# receptor_same.net
KiCad netlist of a schematic drawn in EAGLE
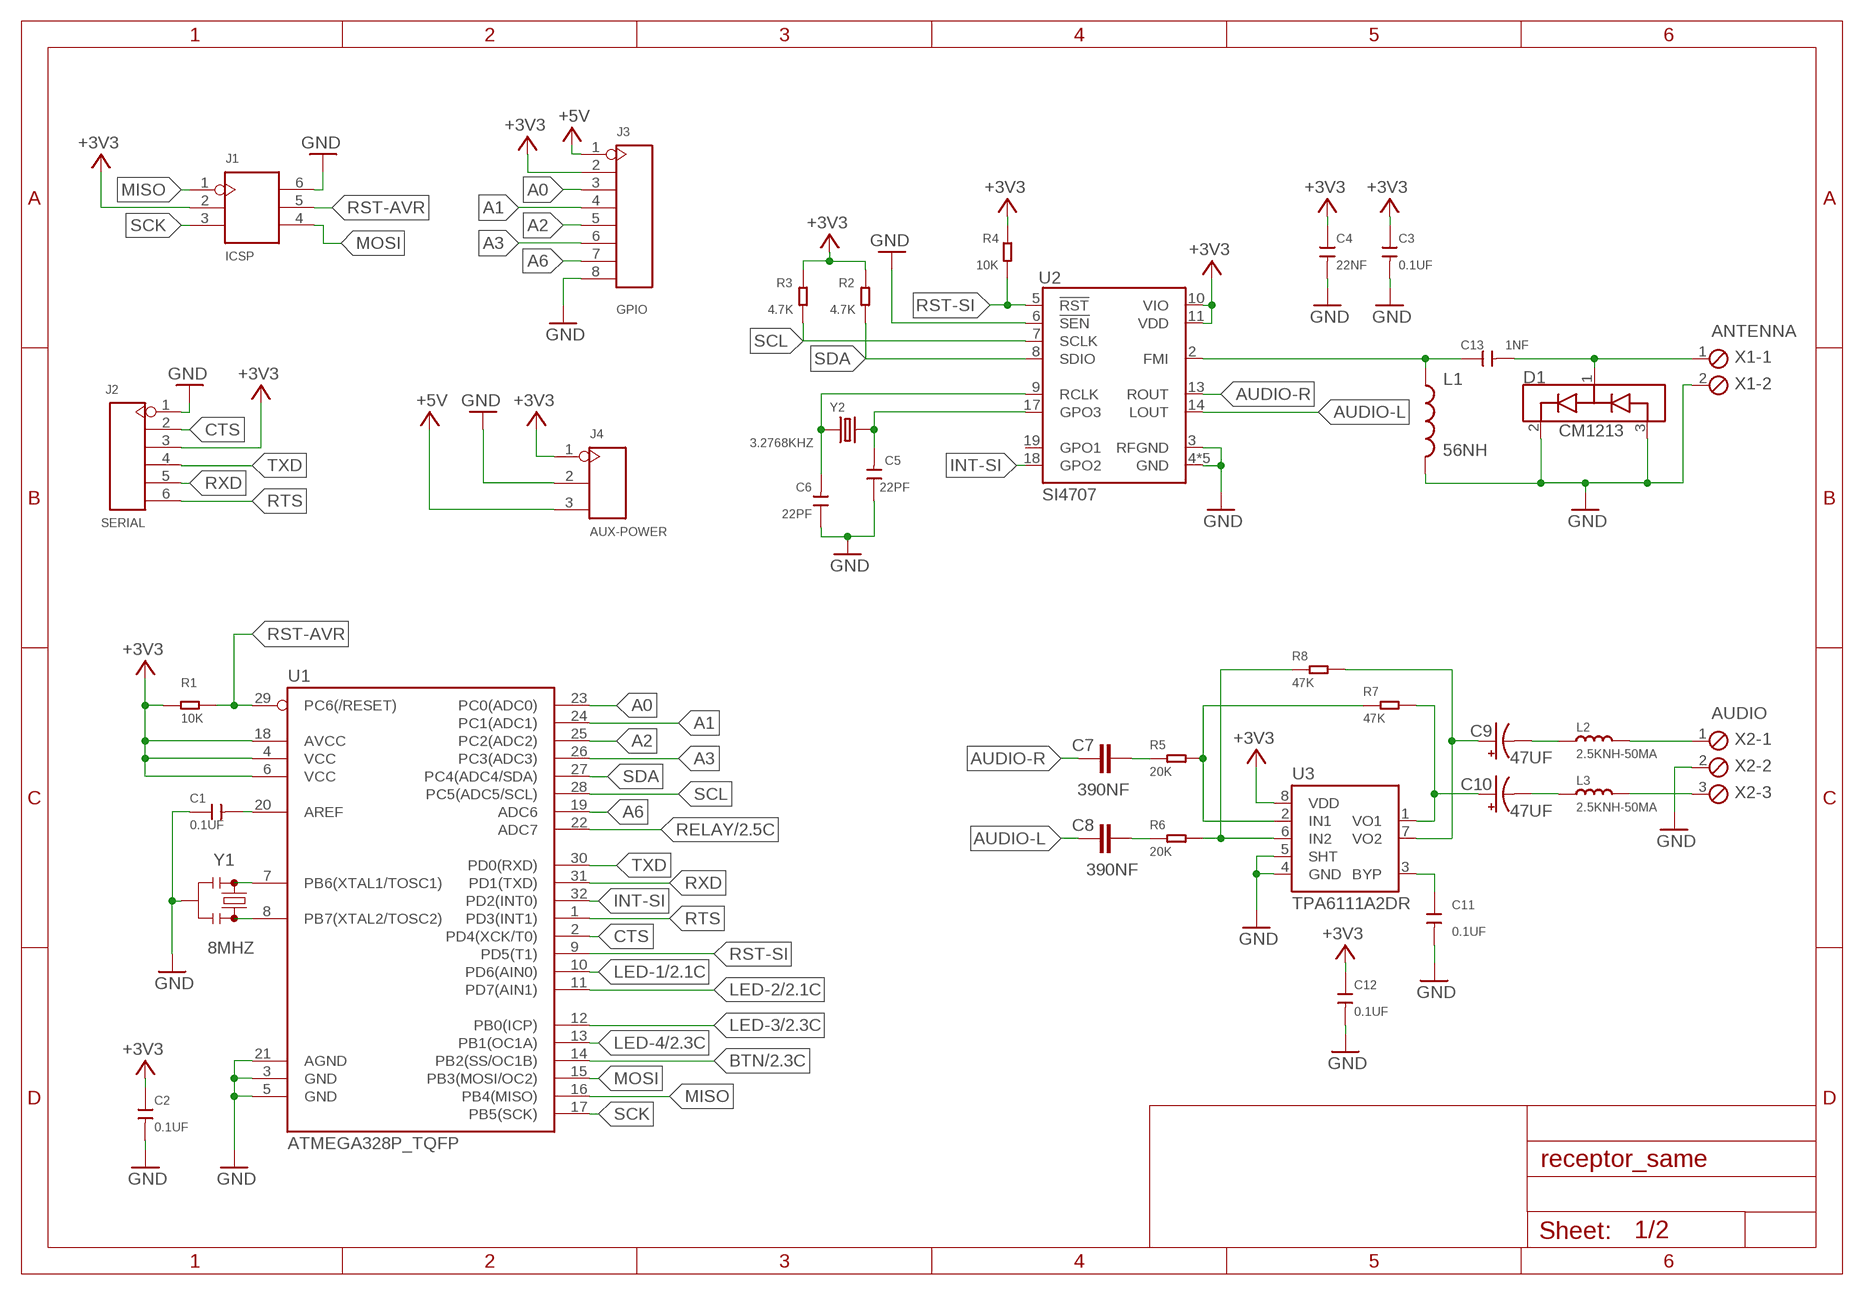
[diagram p0: schematic, sheet 1]
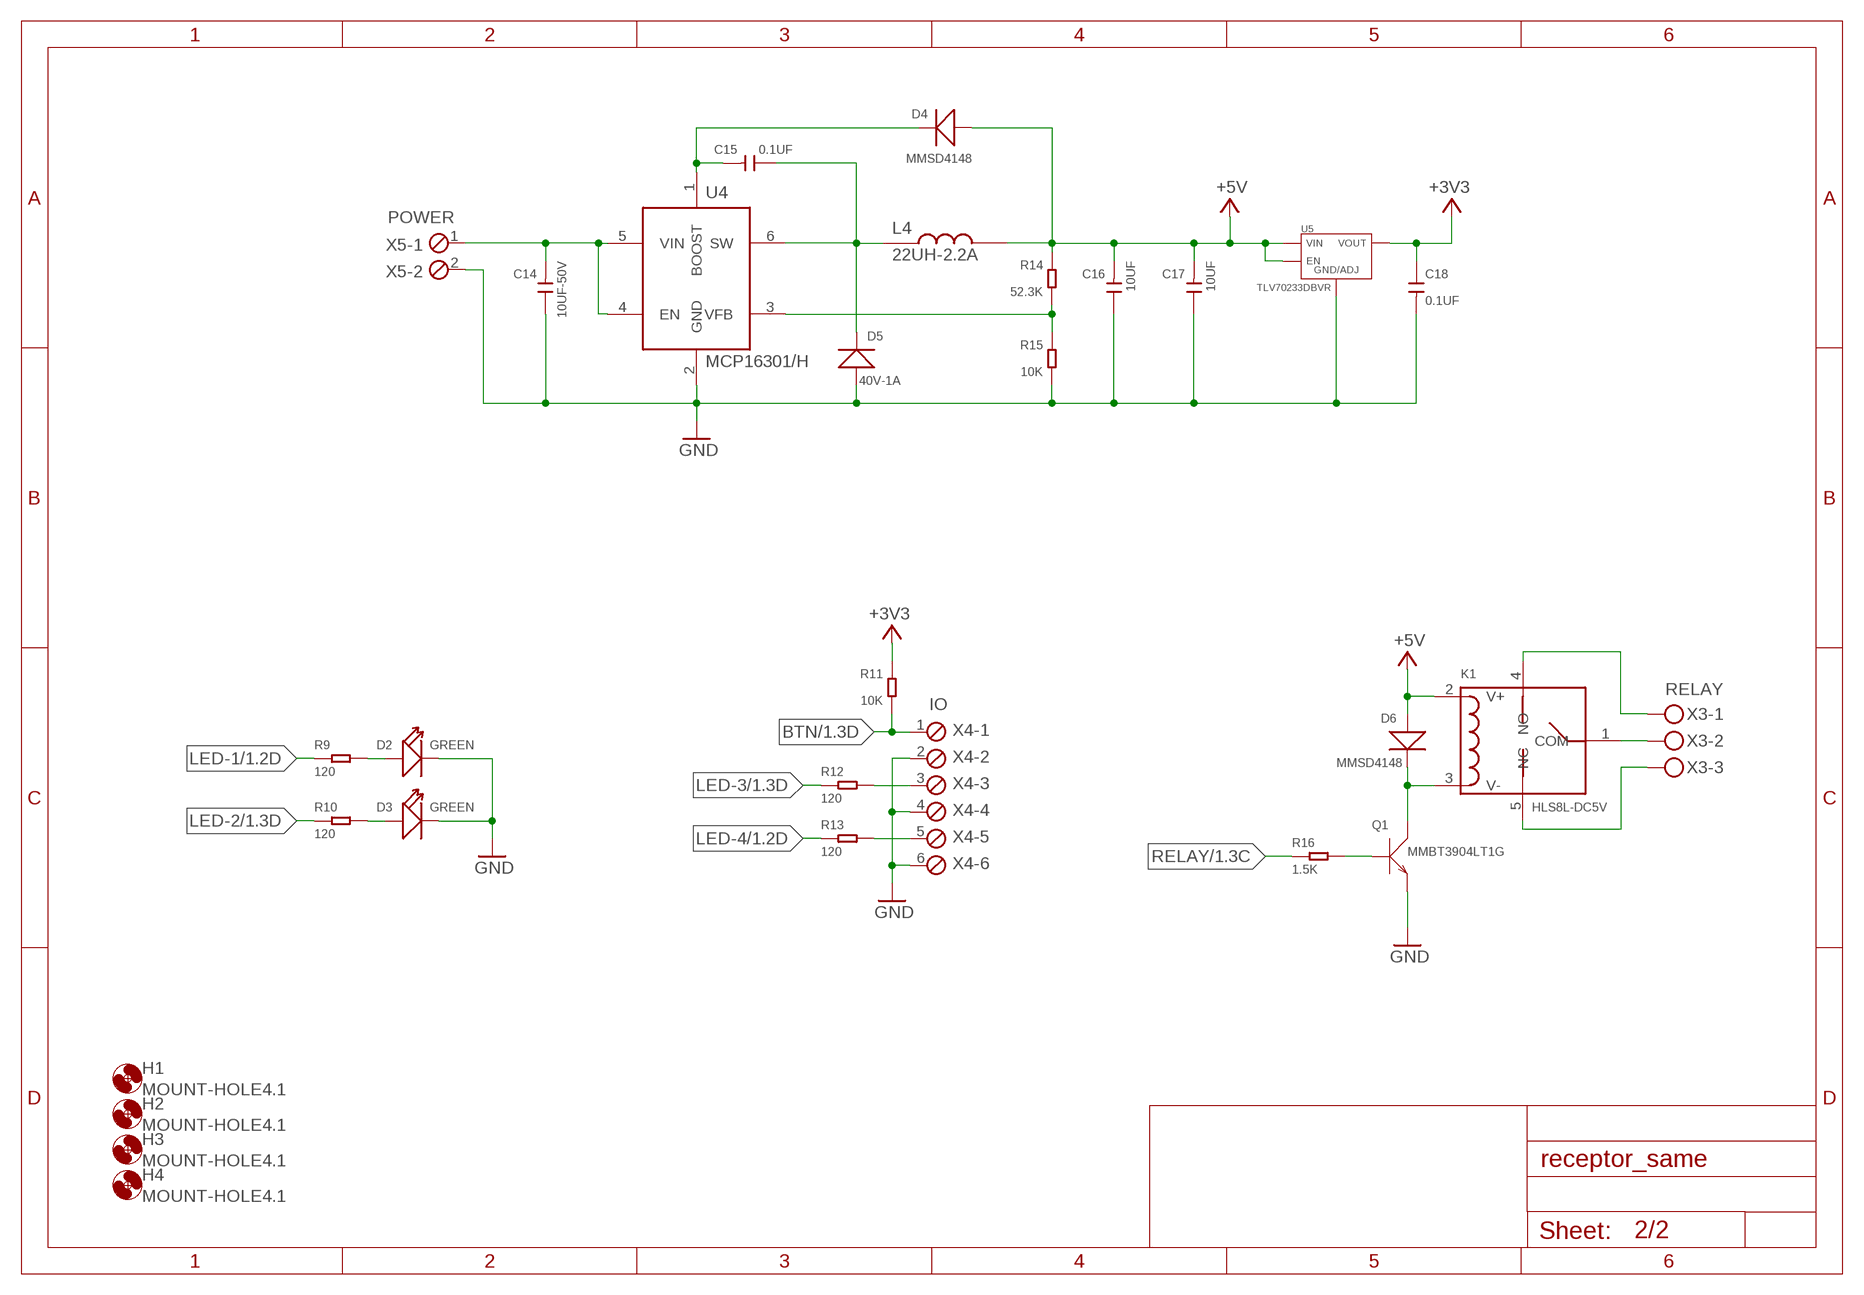
[diagram p1: schematic, sheet 2]

(export (version "E")
  (design (tool "Eeschema 10.0.6"))
  (components
    (comp (ref "C14")
      (value "10UF-50V")
      (footprint "eagle-import:C1206")
      (fields (field (name "MPN") "CC1206KKX5R8BB106") (field (name "MPN_1") "CL31A106KBHNNNE"))
      (libsource (lib "eagle-import") (part "CERAMIC-10UF-25V-10%-X5R(1206)"))
    )
    (comp (ref "C15")
      (value "0.1UF")
      (footprint "eagle-import:C0603")
      (fields (field (name "MPN") "CC0603KRX7R9BB104"))
      (libsource (lib "eagle-import") (part "CERAMIC-100NF-50V-10%-X7R(0603)"))
    )
    (comp (ref "C16")
      (value "10UF")
      (footprint "eagle-import:C0603")
      (fields (field (name "MPN") "CC0603MRX5R5BB106"))
      (libsource (lib "eagle-import") (part "CERAMIC-10UF-6.3V-20%-X5R(0603)"))
    )
    (comp (ref "C17")
      (value "10UF")
      (footprint "eagle-import:C0603")
      (fields (field (name "MPN") "CC0603MRX5R5BB106"))
      (libsource (lib "eagle-import") (part "CERAMIC-10UF-6.3V-20%-X5R(0603)"))
    )
    (comp (ref "C18")
      (value "0.1UF")
      (footprint "eagle-import:C0603")
      (fields (field (name "MPN") "CC0603KRX7R9BB104"))
      (libsource (lib "eagle-import") (part "CERAMIC-100NF-50V-10%-X7R(0603)"))
    )
    (comp (ref "D2")
      (value "GREEN")
      (footprint "eagle-import:LED-0805")
      (fields (field (name "MPN") "17-215SYGC/S530-E2/TR8"))
      (libsource (lib "eagle-import") (part "SMD-LED-CLEAR-GREEN(0805)"))
    )
    (comp (ref "D3")
      (value "GREEN")
      (footprint "eagle-import:LED-0805")
      (fields (field (name "MPN") "17-215SYGC/S530-E2/TR8"))
      (libsource (lib "eagle-import") (part "SMD-LED-CLEAR-GREEN(0805)"))
    )
    (comp (ref "D4")
      (value "MMSD4148")
      (footprint "eagle-import:SOD-123")
      (libsource (lib "eagle-import") (part "SMD-DIODE-100V-200MA(SOD-123)"))
    )
    (comp (ref "D5")
      (value "40V-1A")
      (footprint "eagle-import:DO-214AC")
      (fields (field (name "MPN") "1N5819"))
      (libsource (lib "eagle-import") (part "SMD-DIODE-SCHOTTKY-40V-1A(DO-214AC)"))
    )
    (comp (ref "D6")
      (value "MMSD4148")
      (footprint "eagle-import:SOD-123")
      (libsource (lib "eagle-import") (part "SMD-DIODE-100V-200MA(SOD-123)"))
    )
    (comp (ref "H1")
      (value "MOUNT-HOLE4.1")
      (footprint "eagle-import:4,1")
      (libsource (lib "eagle-import") (part "MOUNT-HOLE4.1"))
    )
    (comp (ref "H2")
      (value "MOUNT-HOLE4.1")
      (footprint "eagle-import:4,1")
      (libsource (lib "eagle-import") (part "MOUNT-HOLE4.1"))
    )
    (comp (ref "H3")
      (value "MOUNT-HOLE4.1")
      (footprint "eagle-import:4,1")
      (libsource (lib "eagle-import") (part "MOUNT-HOLE4.1"))
    )
    (comp (ref "H4")
      (value "MOUNT-HOLE4.1")
      (footprint "eagle-import:4,1")
      (libsource (lib "eagle-import") (part "MOUNT-HOLE4.1"))
    )
    (comp (ref "K1")
      (value "HLS8L-DC5V")
      (footprint "eagle-import:REY5-19.0X15.0X15.0MM")
      (fields (field (name "MPN") "HLS8L-DC5V-S-C"))
      (libsource (lib "eagle-import") (part "RELAY-HLS8L-DC5V-S-CHLS8L-DC5V-S-C"))
    )
    (comp (ref "L4")
      (value "22UH-2.2A")
      (footprint "eagle-import:L2826")
      (fields (field (name "MPN") "SHC0603-220M "))
      (libsource (lib "eagle-import") (part "303010525_22UH_7.1X6.6MM"))
    )
    (comp (ref "Q1")
      (value "MMBT3904LT1G")
      (footprint "eagle-import:SOT-23")
      (libsource (lib "eagle-import") (part "SMD-TRANSISTORS-NPN-40V-200MA-MMBT3904LT1G(SOT-23)"))
    )
    (comp (ref "R9")
      (value "120")
      (footprint "eagle-import:R0805")
      (fields (field (name "MPN") "RC0805JR-071KL") (field (name "MPN_1") "RC0805JR-07120RL"))
      (libsource (lib "eagle-import") (part "SMD-RES-120R-5%-1/8W(0805)"))
    )
    (comp (ref "R10")
      (value "120")
      (footprint "eagle-import:R0805")
      (fields (field (name "MPN") "RC0805JR-071KL") (field (name "MPN_1") "RC0805JR-07120RL"))
      (libsource (lib "eagle-import") (part "SMD-RES-120R-5%-1/8W(0805)"))
    )
    (comp (ref "R11")
      (value "10K")
      (footprint "eagle-import:R0603")
      (fields (field (name "MPN") "RC0603JR-0710KL"))
      (libsource (lib "eagle-import") (part "SMD-RES-10K-5%-1/10W(0603)"))
    )
    (comp (ref "R12")
      (value "120")
      (footprint "eagle-import:R0805")
      (fields (field (name "MPN") "RC0805JR-071KL") (field (name "MPN_1") "RC0805JR-07120RL"))
      (libsource (lib "eagle-import") (part "SMD-RES-120R-5%-1/8W(0805)"))
    )
    (comp (ref "R13")
      (value "120")
      (footprint "eagle-import:R0805")
      (fields (field (name "MPN") "RC0805JR-071KL") (field (name "MPN_1") "RC0805JR-07120RL"))
      (libsource (lib "eagle-import") (part "SMD-RES-120R-5%-1/8W(0805)"))
    )
    (comp (ref "R14")
      (value "52.3K")
      (footprint "eagle-import:R0603")
      (fields (field (name "MPN") "RC0603JR-0751KL") (field (name "MPN_1") "WR06X5232FTL"))
      (libsource (lib "eagle-import") (part "SMD-RES-51K-5%-1/10W(0603)"))
    )
    (comp (ref "R15")
      (value "10K")
      (footprint "eagle-import:R0603")
      (fields (field (name "MPN") "RC0603JR-0710KL"))
      (libsource (lib "eagle-import") (part "SMD-RES-10K-5%-1/10W(0603)"))
    )
    (comp (ref "R16")
      (value "1.5K")
      (footprint "eagle-import:R0603")
      (fields (field (name "MPN") "RC0603JR-071K5L"))
      (libsource (lib "eagle-import") (part "SMD-RES-1.5K-5%-1/10W(0603)"))
    )
    (comp (ref "U4")
      (value "MCP16301/H")
      (footprint "eagle-import:SOT23-6")
      (fields (field (name "MPN") "MCP16301T-I/CHY"))
      (libsource (lib "eagle-import") (part "MCP16301/H"))
    )
    (comp (ref "U5")
      (value "TLV70233DBVR")
      (footprint "eagle-import:SOT-23-5")
      (fields
        (field (name "HOUSEPART") "YES")
        (field (name "MPN") "MF-REG-SOT235-3.3V-300mA")
        (field (name "MPN_1") "TLV70233DBVR")
      )
      (libsource (lib "eagle-import") (part "TLV70233PDBVR"))
    )
    (comp (ref "X3")
      (value "RELAY")
      (footprint "eagle-import:MKDSN1,5_3-5,08")
      (fields (field (name "MPN") "1715734"))
      (libsource (lib "eagle-import") (part "MKDSN1,5/3-5,08"))
    )
    (comp (ref "X4")
      (value "IO")
      (footprint "eagle-import:6POL254")
      (fields (field (name "MPN") "1725698"))
      (libsource (lib "eagle-import") (part "MPT6"))
    )
    (comp (ref "X5")
      (value "POWER")
      (footprint "eagle-import:2POL254")
      (fields (field (name "MPN") "1725656"))
      (libsource (lib "eagle-import") (part "MPT2"))
    )
    (comp (ref "C1")
      (value "0.1UF")
      (footprint "eagle-import:C0603")
      (fields (field (name "MPN") "CC0603KRX7R9BB104"))
      (libsource (lib "eagle-import") (part "CERAMIC-100NF-50V-10%-X7R(0603)"))
    )
    (comp (ref "C2")
      (value "0.1UF")
      (footprint "eagle-import:C0603")
      (fields (field (name "MPN") "CC0603KRX7R9BB104"))
      (libsource (lib "eagle-import") (part "CERAMIC-100NF-50V-10%-X7R(0603)"))
    )
    (comp (ref "C3")
      (value "0.1UF")
      (footprint "eagle-import:C0603")
      (fields (field (name "MPN") "CC0603KRX7R9BB104"))
      (libsource (lib "eagle-import") (part "CERAMIC-100NF-50V-10%-X7R(0603)"))
    )
    (comp (ref "C4")
      (value "22NF")
      (footprint "eagle-import:C0603")
      (fields (field (name "MPN") "CC0603KRX7R9BB223"))
      (libsource (lib "eagle-import") (part "CERAMIC-22NF-50V-10%-X7R(0603)"))
    )
    (comp (ref "C5")
      (value "22PF")
      (footprint "eagle-import:C0603")
      (fields (field (name "MPN") "CC0603JRNPO9BN220") (field (name "SPICEPREFIX") "C"))
      (libsource (lib "eagle-import") (part "CERAMIC-22PF-50V-5%-NPO(0603)"))
    )
    (comp (ref "C6")
      (value "22PF")
      (footprint "eagle-import:C0603")
      (fields (field (name "MPN") "CC0603JRNPO9BN220") (field (name "SPICEPREFIX") "C"))
      (libsource (lib "eagle-import") (part "CERAMIC-22PF-50V-5%-NPO(0603)"))
    )
    (comp (ref "C7")
      (value "390NF")
      (footprint "eagle-import:0603")
      (fields (field (name "MPN") "CC0603KRX7R6BB394") (field (name "SPICEPREFIX") "C"))
      (libsource (lib "eagle-import") (part "390NF-0603-10V-10%"))
    )
    (comp (ref "C8")
      (value "390NF")
      (footprint "eagle-import:0603")
      (fields (field (name "MPN") "CC0603KRX7R6BB394") (field (name "SPICEPREFIX") "C"))
      (libsource (lib "eagle-import") (part "390NF-0603-10V-10%"))
    )
    (comp (ref "C9")
      (value "47UF")
      (footprint "eagle-import:EIA3528")
      (fields (field (name "MPN") "TAJB476K010RNJ") (field (name "SPICEPREFIX") "C"))
      (libsource (lib "eagle-import") (part "47UF-POLAR-EIA3528-10V-10%"))
    )
    (comp (ref "C10")
      (value "47UF")
      (footprint "eagle-import:EIA3528")
      (fields (field (name "MPN") "TAJB476K010RNJ") (field (name "SPICEPREFIX") "C"))
      (libsource (lib "eagle-import") (part "47UF-POLAR-EIA3528-10V-10%"))
    )
    (comp (ref "C11")
      (value "0.1UF")
      (footprint "eagle-import:C0603")
      (fields (field (name "MPN") "CC0603KRX7R9BB104"))
      (libsource (lib "eagle-import") (part "CERAMIC-100NF-50V-10%-X7R(0603)"))
    )
    (comp (ref "C12")
      (value "0.1UF")
      (footprint "eagle-import:C0603")
      (fields (field (name "MPN") "CC0603KRX7R9BB104"))
      (libsource (lib "eagle-import") (part "CERAMIC-100NF-50V-10%-X7R(0603)"))
    )
    (comp (ref "C13")
      (value "1NF")
      (footprint "eagle-import:C0603")
      (fields (field (name "MPN") "GRM1885C1H102JA01D"))
      (libsource (lib "eagle-import") (part "CERAMIC-1NF-50V-5%-C0G(0603)"))
    )
    (comp (ref "D1")
      (value "CM1213")
      (footprint "eagle-import:SPARKFUN-DISCRETESEMI_SOT23-3")
      (fields (field (name "MPN") "CM1213A-01SO"))
      (libsource (lib "eagle-import") (part "SPARKFUN-DISCRETESEMI_CM1213"))
    )
    (comp (ref "J1")
      (value "ICSP")
      (footprint "eagle-import:H2X3-2.54")
      (fields (field (name "MPN") "P125-12A1BS116A1"))
      (libsource (lib "eagle-import") (part "DIP-BLACK-MALE-HEADER(2X3P-2.54）-2.54"))
    )
    (comp (ref "J2")
      (value "SERIAL")
      (footprint "eagle-import:H6-2.54")
      (fields (field (name "MPN") "P125-1106A1BS116A1") (field (name "SPICEPREFIX") "X"))
      (libsource (lib "eagle-import") (part "DIP-BLACK-MALE-HEADER(6P-2.54)"))
    )
    (comp (ref "J3")
      (value "GPIO")
      (footprint "eagle-import:H8-2.54")
      (fields (field (name "MPN") "P125-1108A1BS116A1"))
      (libsource (lib "eagle-import") (part "DIP-BLACK-MALE-HEADER-VERT(8P-2.54)"))
    )
    (comp (ref "J4")
      (value "AUX-POWER")
      (footprint "eagle-import:H3-2.54")
      (fields (field (name "MPN") "P125-1103A1BS116A1"))
      (libsource (lib "eagle-import") (part "DIP-BLACK-MALE-HEADER-VERT(3P-2.54)"))
    )
    (comp (ref "L1")
      (value "56NH")
      (footprint "eagle-import:SPARKFUN-PASSIVES_0603")
      (fields (field (name "MPN") "SDCL1608C56NJTDF"))
      (libsource (lib "eagle-import") (part "SPARKFUN-PASSIVES_INDUCTOR0603"))
    )
    (comp (ref "L2")
      (value "2.5KNH-50MA")
      (footprint "eagle-import:L0402")
      (fields
        (field (name "MPN") "LQG15HS4N7S02")
        (field (name "MPN_1") "BLM18BD252SN1D")
        (field (name "SPICEPREFIX") "L")
      )
      (libsource (lib "eagle-import") (part "SMD-INDUCTOR-4.7NH-0.3NH-300MA(0402)"))
    )
    (comp (ref "L3")
      (value "2.5KNH-50MA")
      (footprint "eagle-import:L0402")
      (fields
        (field (name "MPN") "LQG15HS4N7S02")
        (field (name "MPN_1") "BLM18BD252SN1D")
        (field (name "SPICEPREFIX") "L")
      )
      (libsource (lib "eagle-import") (part "SMD-INDUCTOR-4.7NH-0.3NH-300MA(0402)"))
    )
    (comp (ref "R1")
      (value "10K")
      (footprint "eagle-import:R0603")
      (fields (field (name "MPN") "RC0603JR-0710KL"))
      (libsource (lib "eagle-import") (part "SMD-RES-10K-5%-1/10W(0603)"))
    )
    (comp (ref "R2")
      (value "4.7K")
      (footprint "eagle-import:R0603")
      (fields (field (name "MPN") "RC0603JR-074K7L"))
      (libsource (lib "eagle-import") (part "SMD-RES-4.7K-5%-1/10W(0603)"))
    )
    (comp (ref "R3")
      (value "4.7K")
      (footprint "eagle-import:R0603")
      (fields (field (name "MPN") "RC0603JR-074K7L"))
      (libsource (lib "eagle-import") (part "SMD-RES-4.7K-5%-1/10W(0603)"))
    )
    (comp (ref "R4")
      (value "10K")
      (footprint "eagle-import:R0603")
      (fields (field (name "MPN") "RC0603JR-0710KL"))
      (libsource (lib "eagle-import") (part "SMD-RES-10K-5%-1/10W(0603)"))
    )
    (comp (ref "R5")
      (value "20K")
      (footprint "eagle-import:R0603")
      (fields (field (name "MPN") "RC0603FR-0720KL") (field (name "SPICEPREFIX") "R"))
      (libsource (lib "eagle-import") (part "SMD-RES-20K-1%-1/10W(0603)"))
    )
    (comp (ref "R6")
      (value "20K")
      (footprint "eagle-import:R0603")
      (fields (field (name "MPN") "RC0603FR-0720KL") (field (name "SPICEPREFIX") "R"))
      (libsource (lib "eagle-import") (part "SMD-RES-20K-1%-1/10W(0603)"))
    )
    (comp (ref "R7")
      (value "47K")
      (footprint "eagle-import:R0603")
      (fields (field (name "MPN") "RC0603JR-0747KL") (field (name "SPICEPREFIX") "R"))
      (libsource (lib "eagle-import") (part "SMD-RES-47K-5%-1/10W(0603)"))
    )
    (comp (ref "R8")
      (value "47K")
      (footprint "eagle-import:R0603")
      (fields (field (name "MPN") "RC0603JR-0747KL") (field (name "SPICEPREFIX") "R"))
      (libsource (lib "eagle-import") (part "SMD-RES-47K-5%-1/10W(0603)"))
    )
    (comp (ref "U1")
      (value "ATMEGA328P_TQFP")
      (footprint "eagle-import:TQFP32-08")
      (fields (field (name "MPN") "ATMEGA328P-AU"))
      (libsource (lib "eagle-import") (part "ATMEGA328P_TQFP"))
    )
    (comp (ref "U2")
      (value "SI4707")
      (footprint "eagle-import:SPARKFUN-RF_SI470X")
      (fields (field (name "MPN") "SI4707-B20-GM") (field (name "SPICEPREFIX") "X"))
      (libsource (lib "eagle-import") (part "SPARKFUN-RF_SI4707"))
    )
    (comp (ref "U3")
      (value "TPA6111A2DR")
      (footprint "eagle-import:SO08")
      (fields (field (name "SPICEPREFIX") "X"))
      (libsource (lib "eagle-import") (part "TPA6111SMD-T"))
    )
    (comp (ref "X1")
      (value "ANTENNA")
      (footprint "eagle-import:2POL254")
      (fields (field (name "MPN") "1725656"))
      (libsource (lib "eagle-import") (part "MPT2"))
    )
    (comp (ref "X2")
      (value "AUDIO")
      (footprint "eagle-import:3POL254")
      (fields (field (name "MPN") "1725669") (field (name "SPICEPREFIX") "X"))
      (libsource (lib "eagle-import") (part "MPT3"))
    )
    (comp (ref "Y1")
      (value "8MHZ")
      (footprint "eagle-import:RESONATOR-SMD-3.2X1.3")
      (fields (field (name "MPN") "CSTCE8M00G55-R0"))
      (libsource (lib "eagle-import") (part "RESONATOR-8MHZSMD_3.2X1.3"))
    )
    (comp (ref "Y2")
      (value "3.2768KHZ")
      (footprint "eagle-import:X2-SMD-L2.0X1.2X0.55MM")
      (fields (field (name "MPN") "FC-12M") (field (name "SPICEPREFIX") "B"))
      (libsource (lib "eagle-import") (part "SMD-CRYSTAL-32.768KHZ-12.5PF-20PPM-90K(2P-L2.0X1.2MM)"))
    )
  )
  (nets
    (net (code "1") (name "+3V3") (class "Default")
      (node (ref "C12") (pin "1") (pinfunction "1_1") (pintype "passive"))
      (node (ref "C18") (pin "1") (pinfunction "1_1") (pintype "passive"))
      (node (ref "C2") (pin "1") (pinfunction "1_1") (pintype "passive"))
      (node (ref "C3") (pin "1") (pinfunction "1_1") (pintype "passive"))
      (node (ref "C4") (pin "1") (pinfunction "1_1") (pintype "passive"))
      (node (ref "J1") (pin "2") (pinfunction "2_2") (pintype "bidirectional"))
      (node (ref "J2") (pin "3") (pinfunction "3_3") (pintype "bidirectional"))
      (node (ref "J3") (pin "2") (pinfunction "2_2") (pintype "bidirectional"))
      (node (ref "J4") (pin "1") (pinfunction "P$1_1") (pintype "bidirectional"))
      (node (ref "R1") (pin "2") (pinfunction "2_2") (pintype "passive"))
      (node (ref "R11") (pin "1") (pinfunction "1_1") (pintype "passive"))
      (node (ref "R2") (pin "1") (pinfunction "1_1") (pintype "passive"))
      (node (ref "R3") (pin "1") (pinfunction "1_1") (pintype "passive"))
      (node (ref "R4") (pin "1") (pinfunction "1_1") (pintype "passive"))
      (node (ref "U1") (pin "18") (pinfunction "AVCC_18") (pintype "bidirectional"))
      (node (ref "U1") (pin "4") (pinfunction "VCC_4") (pintype "bidirectional"))
      (node (ref "U1") (pin "6") (pinfunction "VCC_6") (pintype "bidirectional"))
      (node (ref "U2") (pin "10") (pinfunction "VIO_10") (pintype "bidirectional"))
      (node (ref "U2") (pin "11") (pinfunction "VDD_11") (pintype "bidirectional"))
      (node (ref "U3") (pin "8") (pinfunction "VDD_8") (pintype "bidirectional"))
      (node (ref "U5") (pin "P$5") (pinfunction "VOUT_P$5") (pintype "bidirectional"))
    )
    (net (code "2") (name "+5V") (class "Default")
      (node (ref "C16") (pin "2") (pinfunction "2_2") (pintype "passive"))
      (node (ref "C17") (pin "2") (pinfunction "2_2") (pintype "passive"))
      (node (ref "D4") (pin "+") (pinfunction "+_+") (pintype "passive"))
      (node (ref "D6") (pin "+") (pinfunction "+_+") (pintype "passive"))
      (node (ref "J3") (pin "1") (pinfunction "1_1") (pintype "bidirectional"))
      (node (ref "J4") (pin "3") (pinfunction "P$3_3") (pintype "bidirectional"))
      (node (ref "K1") (pin "2") (pinfunction "V+_2") (pintype "bidirectional"))
      (node (ref "L4") (pin "P$2") (pinfunction "P$2_P$2") (pintype "passive"))
      (node (ref "R14") (pin "2") (pinfunction "2_2") (pintype "passive"))
      (node (ref "U5") (pin "P$1") (pinfunction "VIN_P$1") (pintype "bidirectional"))
      (node (ref "U5") (pin "P$3") (pinfunction "EN_P$3") (pintype "bidirectional"))
    )
    (net (code "3") (name "A0") (class "Default")
      (node (ref "J3") (pin "3") (pinfunction "3_3") (pintype "bidirectional"))
      (node (ref "U1") (pin "23") (pinfunction "PC0(ADC0)_23") (pintype "bidirectional"))
    )
    (net (code "4") (name "A1") (class "Default")
      (node (ref "J3") (pin "4") (pinfunction "4_4") (pintype "bidirectional"))
      (node (ref "U1") (pin "24") (pinfunction "PC1(ADC1)_24") (pintype "bidirectional"))
    )
    (net (code "5") (name "A2") (class "Default")
      (node (ref "J3") (pin "5") (pinfunction "5_5") (pintype "bidirectional"))
      (node (ref "U1") (pin "25") (pinfunction "PC2(ADC2)_25") (pintype "bidirectional"))
    )
    (net (code "6") (name "A3") (class "Default")
      (node (ref "J3") (pin "6") (pinfunction "6_6") (pintype "bidirectional"))
      (node (ref "U1") (pin "26") (pinfunction "PC3(ADC3)_26") (pintype "bidirectional"))
    )
    (net (code "7") (name "A6") (class "Default")
      (node (ref "J3") (pin "7") (pinfunction "7_7") (pintype "bidirectional"))
      (node (ref "U1") (pin "19") (pinfunction "ADC6_19") (pintype "bidirectional"))
    )
    (net (code "8") (name "AUDIO-L") (class "Default")
      (node (ref "C8") (pin "1") (pinfunction "1_1") (pintype "passive"))
      (node (ref "U2") (pin "14") (pinfunction "LOUT_14") (pintype "bidirectional"))
    )
    (net (code "9") (name "AUDIO-R") (class "Default")
      (node (ref "C7") (pin "1") (pinfunction "1_1") (pintype "passive"))
      (node (ref "U2") (pin "13") (pinfunction "ROUT_13") (pintype "bidirectional"))
    )
    (net (code "10") (name "BTN") (class "Default")
      (node (ref "R11") (pin "2") (pinfunction "2_2") (pintype "passive"))
      (node (ref "U1") (pin "14") (pinfunction "PB2(SS/OC1B)_14") (pintype "bidirectional"))
      (node (ref "X4") (pin "1") (pinfunction "1_1") (pintype "passive"))
    )
    (net (code "11") (name "CTS") (class "Default")
      (node (ref "J2") (pin "2") (pinfunction "2_2") (pintype "bidirectional"))
      (node (ref "U1") (pin "2") (pinfunction "PD4(XCK/T0)_2") (pintype "bidirectional"))
    )
    (net (code "12") (name "GND") (class "Default")
      (node (ref "C1") (pin "1") (pinfunction "1_1") (pintype "passive"))
      (node (ref "C11") (pin "2") (pinfunction "2_2") (pintype "passive"))
      (node (ref "C12") (pin "2") (pinfunction "2_2") (pintype "passive"))
      (node (ref "C14") (pin "1") (pinfunction "1_1") (pintype "passive"))
      (node (ref "C16") (pin "1") (pinfunction "1_1") (pintype "passive"))
      (node (ref "C17") (pin "1") (pinfunction "1_1") (pintype "passive"))
      (node (ref "C18") (pin "2") (pinfunction "2_2") (pintype "passive"))
      (node (ref "C2") (pin "2") (pinfunction "2_2") (pintype "passive"))
      (node (ref "C3") (pin "2") (pinfunction "2_2") (pintype "passive"))
      (node (ref "C4") (pin "2") (pinfunction "2_2") (pintype "passive"))
      (node (ref "C5") (pin "1") (pinfunction "1_1") (pintype "passive"))
      (node (ref "C6") (pin "1") (pinfunction "1_1") (pintype "passive"))
      (node (ref "D1") (pin "2") (pinfunction "VP_2") (pintype "bidirectional"))
      (node (ref "D1") (pin "3") (pinfunction "VN_3") (pintype "bidirectional"))
      (node (ref "D2") (pin "-") (pinfunction "-_-") (pintype "passive"))
      (node (ref "D3") (pin "-") (pinfunction "-_-") (pintype "passive"))
      (node (ref "D5") (pin "1") (pinfunction "+_1") (pintype "passive"))
      (node (ref "J1") (pin "6") (pinfunction "6_6") (pintype "bidirectional"))
      (node (ref "J2") (pin "1") (pinfunction "1_1") (pintype "bidirectional"))
      (node (ref "J3") (pin "8") (pinfunction "8_8") (pintype "bidirectional"))
      (node (ref "J4") (pin "2") (pinfunction "P$2_2") (pintype "bidirectional"))
      (node (ref "L1") (pin "2") (pinfunction "2_2") (pintype "passive"))
      (node (ref "Q1") (pin "2") (pinfunction "E_2") (pintype "passive"))
      (node (ref "R15") (pin "2") (pinfunction "2_2") (pintype "passive"))
      (node (ref "U1") (pin "21") (pinfunction "AGND_21") (pintype "bidirectional"))
      (node (ref "U1") (pin "3") (pinfunction "GND_3") (pintype "bidirectional"))
      (node (ref "U1") (pin "5") (pinfunction "GND_5") (pintype "bidirectional"))
      (node (ref "U2") (pin "12") (pinfunction "GND_12") (pintype "bidirectional"))
      (node (ref "U2") (pin "15") (pinfunction "GND_15") (pintype "bidirectional"))
      (node (ref "U2") (pin "16") (pinfunction "GND_16") (pintype "bidirectional"))
      (node (ref "U2") (pin "21") (pinfunction "GND_21") (pintype "bidirectional"))
      (node (ref "U2") (pin "3") (pinfunction "RFGND_3") (pintype "bidirectional"))
      (node (ref "U2") (pin "4") (pinfunction "GND_4") (pintype "bidirectional"))
      (node (ref "U2") (pin "6") (pinfunction "~{SEN}_6") (pintype "bidirectional"))
      (node (ref "U3") (pin "4") (pinfunction "GND_4") (pintype "bidirectional"))
      (node (ref "U3") (pin "5") (pinfunction "SHT_5") (pintype "bidirectional"))
      (node (ref "U4") (pin "2") (pinfunction "GND_2") (pintype "power_in"))
      (node (ref "U5") (pin "P$2") (pinfunction "GND/ADJ_P$2") (pintype "bidirectional"))
      (node (ref "X1") (pin "2") (pinfunction "1_2") (pintype "passive"))
      (node (ref "X2") (pin "2") (pinfunction "1_2") (pintype "passive"))
      (node (ref "X4") (pin "2") (pinfunction "1_2") (pintype "passive"))
      (node (ref "X4") (pin "4") (pinfunction "1_4") (pintype "passive"))
      (node (ref "X4") (pin "6") (pinfunction "1_6") (pintype "passive"))
      (node (ref "X5") (pin "2") (pinfunction "1_2") (pintype "passive"))
      (node (ref "Y1") (pin "2") (pinfunction "2_2") (pintype "passive"))
    )
    (net (code "13") (name "INT-SI") (class "Default")
      (node (ref "U1") (pin "32") (pinfunction "PD2(INT0)_32") (pintype "bidirectional"))
      (node (ref "U2") (pin "18") (pinfunction "GPO2_18") (pintype "bidirectional"))
    )
    (net (code "14") (name "LED-1") (class "Default")
      (node (ref "R9") (pin "1") (pinfunction "1_1") (pintype "passive"))
      (node (ref "U1") (pin "10") (pinfunction "PD6(AIN0)_10") (pintype "bidirectional"))
    )
    (net (code "15") (name "LED-2") (class "Default")
      (node (ref "R10") (pin "1") (pinfunction "1_1") (pintype "passive"))
      (node (ref "U1") (pin "11") (pinfunction "PD7(AIN1)_11") (pintype "bidirectional"))
    )
    (net (code "16") (name "LED-3") (class "Default")
      (node (ref "R12") (pin "1") (pinfunction "1_1") (pintype "passive"))
      (node (ref "U1") (pin "12") (pinfunction "PB0(ICP)_12") (pintype "bidirectional"))
    )
    (net (code "17") (name "LED-4") (class "Default")
      (node (ref "R13") (pin "1") (pinfunction "1_1") (pintype "passive"))
      (node (ref "U1") (pin "13") (pinfunction "PB1(OC1A)_13") (pintype "bidirectional"))
    )
    (net (code "18") (name "MISO") (class "Default")
      (node (ref "J1") (pin "1") (pinfunction "1_1") (pintype "bidirectional"))
      (node (ref "U1") (pin "16") (pinfunction "PB4(MISO)_16") (pintype "bidirectional"))
    )
    (net (code "19") (name "MOSI") (class "Default")
      (node (ref "J1") (pin "4") (pinfunction "4_4") (pintype "bidirectional"))
      (node (ref "U1") (pin "15") (pinfunction "PB3(MOSI/OC2)_15") (pintype "bidirectional"))
    )
    (net (code "20") (name "Net-(C7-Pad2)") (class "Default")
      (node (ref "C7") (pin "2") (pinfunction "2_2") (pintype "passive"))
      (node (ref "R5") (pin "1") (pinfunction "1_1") (pintype "passive"))
    )
    (net (code "21") (name "Net-(C8-Pad2)") (class "Default")
      (node (ref "C8") (pin "2") (pinfunction "2_2") (pintype "passive"))
      (node (ref "R6") (pin "1") (pinfunction "1_1") (pintype "passive"))
    )
    (net (code "22") (name "Net-(C9-+)") (class "Default")
      (node (ref "C9") (pin "A") (pinfunction "+_A") (pintype "passive"))
      (node (ref "R8") (pin "2") (pinfunction "2_2") (pintype "passive"))
      (node (ref "U3") (pin "7") (pinfunction "VO2_7") (pintype "bidirectional"))
    )
    (net (code "23") (name "Net-(C9--)") (class "Default")
      (node (ref "C9") (pin "C") (pinfunction "-_C") (pintype "passive"))
      (node (ref "L2") (pin "1") (pinfunction "1_1") (pintype "passive"))
    )
    (net (code "24") (name "Net-(C10-+)") (class "Default")
      (node (ref "C10") (pin "A") (pinfunction "+_A") (pintype "passive"))
      (node (ref "R7") (pin "2") (pinfunction "2_2") (pintype "passive"))
      (node (ref "U3") (pin "1") (pinfunction "VO1_1") (pintype "bidirectional"))
    )
    (net (code "25") (name "Net-(C10--)") (class "Default")
      (node (ref "C10") (pin "C") (pinfunction "-_C") (pintype "passive"))
      (node (ref "L3") (pin "1") (pinfunction "1_1") (pintype "passive"))
    )
    (net (code "26") (name "Net-(D1-CH1)") (class "Default")
      (node (ref "C13") (pin "2") (pinfunction "2_2") (pintype "passive"))
      (node (ref "D1") (pin "1") (pinfunction "CH1_1") (pintype "bidirectional"))
      (node (ref "X1") (pin "1") (pinfunction "1_1") (pintype "passive"))
    )
    (net (code "27") (name "Net-(D2-Pad+)") (class "Default")
      (node (ref "D2") (pin "+") (pinfunction "+_+") (pintype "passive"))
      (node (ref "R9") (pin "2") (pinfunction "2_2") (pintype "passive"))
    )
    (net (code "28") (name "Net-(D3-Pad+)") (class "Default")
      (node (ref "D3") (pin "+") (pinfunction "+_+") (pintype "passive"))
      (node (ref "R10") (pin "2") (pinfunction "2_2") (pintype "passive"))
    )
    (net (code "29") (name "Net-(D5--)") (class "Default")
      (node (ref "C15") (pin "1") (pinfunction "1_1") (pintype "passive"))
      (node (ref "D5") (pin "2") (pinfunction "-_2") (pintype "passive"))
      (node (ref "L4") (pin "P$1") (pinfunction "P$1_P$1") (pintype "passive"))
      (node (ref "U4") (pin "6") (pinfunction "SW_6") (pintype "power_in"))
    )
    (net (code "30") (name "Net-(K1-COM)") (class "Default")
      (node (ref "K1") (pin "1") (pinfunction "COM_1") (pintype "bidirectional"))
      (node (ref "X3") (pin "2") (pinfunction "KL_2") (pintype "passive"))
    )
    (net (code "31") (name "Net-(K1-NC)") (class "Default")
      (node (ref "K1") (pin "5") (pinfunction "NC_5") (pintype "bidirectional"))
      (node (ref "X3") (pin "3") (pinfunction "KL_3") (pintype "passive"))
    )
    (net (code "32") (name "Net-(K1-NO)") (class "Default")
      (node (ref "K1") (pin "4") (pinfunction "NO_4") (pintype "bidirectional"))
      (node (ref "X3") (pin "1") (pinfunction "KL_1") (pintype "passive"))
    )
    (net (code "33") (name "Net-(K1-V-)") (class "Default")
      (node (ref "D6") (pin "-") (pinfunction "-_-") (pintype "passive"))
      (node (ref "K1") (pin "3") (pinfunction "V-_3") (pintype "bidirectional"))
      (node (ref "Q1") (pin "3") (pinfunction "C_3") (pintype "passive"))
    )
    (net (code "34") (name "Net-(L2-Pad2)") (class "Default")
      (node (ref "L2") (pin "2") (pinfunction "2_2") (pintype "passive"))
      (node (ref "X2") (pin "1") (pinfunction "1_1") (pintype "passive"))
    )
    (net (code "35") (name "Net-(Q1-B)") (class "Default")
      (node (ref "Q1") (pin "1") (pinfunction "B_1") (pintype "passive"))
      (node (ref "R16") (pin "2") (pinfunction "2_2") (pintype "passive"))
    )
    (net (code "36") (name "Net-(U1-AREF)") (class "Default")
      (node (ref "C1") (pin "2") (pinfunction "2_2") (pintype "passive"))
      (node (ref "U1") (pin "20") (pinfunction "AREF_20") (pintype "bidirectional"))
    )
    (net (code "37") (name "Net-(U1-PB6(XTAL1{slash}TOSC1))") (class "Default")
      (node (ref "U1") (pin "7") (pinfunction "PB6(XTAL1/TOSC1)_7") (pintype "bidirectional"))
      (node (ref "Y1") (pin "1") (pinfunction "1_1") (pintype "passive"))
    )
    (net (code "38") (name "Net-(U1-PB7(XTAL2{slash}TOSC2))") (class "Default")
      (node (ref "U1") (pin "8") (pinfunction "PB7(XTAL2/TOSC2)_8") (pintype "bidirectional"))
      (node (ref "Y1") (pin "3") (pinfunction "3_3") (pintype "passive"))
    )
    (net (code "39") (name "Net-(U2-FMI)") (class "Default")
      (node (ref "C13") (pin "1") (pinfunction "1_1") (pintype "passive"))
      (node (ref "L1") (pin "1") (pinfunction "1_1") (pintype "passive"))
      (node (ref "U2") (pin "2") (pinfunction "FMI_2") (pintype "bidirectional"))
    )
    (net (code "40") (name "Net-(U2-GPO3)") (class "Default")
      (node (ref "C5") (pin "2") (pinfunction "2_2") (pintype "passive"))
      (node (ref "U2") (pin "17") (pinfunction "GPO3_17") (pintype "bidirectional"))
      (node (ref "Y2") (pin "2") (pinfunction "2_2") (pintype "passive"))
    )
    (net (code "41") (name "Net-(U2-RCLK)") (class "Default")
      (node (ref "C6") (pin "2") (pinfunction "2_2") (pintype "passive"))
      (node (ref "U2") (pin "9") (pinfunction "RCLK_9") (pintype "bidirectional"))
      (node (ref "Y2") (pin "1") (pinfunction "1_1") (pintype "passive"))
    )
    (net (code "42") (name "Net-(U3-BYP)") (class "Default")
      (node (ref "C11") (pin "1") (pinfunction "1_1") (pintype "passive"))
      (node (ref "U3") (pin "3") (pinfunction "BYP_3") (pintype "bidirectional"))
    )
    (net (code "43") (name "Net-(U3-IN1)") (class "Default")
      (node (ref "R5") (pin "2") (pinfunction "2_2") (pintype "passive"))
      (node (ref "R7") (pin "1") (pinfunction "1_1") (pintype "passive"))
      (node (ref "U3") (pin "2") (pinfunction "IN1_2") (pintype "bidirectional"))
    )
    (net (code "44") (name "Net-(U3-IN2)") (class "Default")
      (node (ref "R6") (pin "2") (pinfunction "2_2") (pintype "passive"))
      (node (ref "R8") (pin "1") (pinfunction "1_1") (pintype "passive"))
      (node (ref "U3") (pin "6") (pinfunction "IN2_6") (pintype "bidirectional"))
    )
    (net (code "45") (name "Net-(U4-BOOST)") (class "Default")
      (node (ref "C15") (pin "2") (pinfunction "2_2") (pintype "passive"))
      (node (ref "D4") (pin "-") (pinfunction "-_-") (pintype "passive"))
      (node (ref "U4") (pin "1") (pinfunction "BOOST_1") (pintype "bidirectional"))
    )
    (net (code "46") (name "Net-(U4-EN)") (class "Default")
      (node (ref "C14") (pin "2") (pinfunction "2_2") (pintype "passive"))
      (node (ref "U4") (pin "4") (pinfunction "EN_4") (pintype "bidirectional"))
      (node (ref "U4") (pin "5") (pinfunction "VIN_5") (pintype "power_in"))
      (node (ref "X5") (pin "1") (pinfunction "1_1") (pintype "passive"))
    )
    (net (code "47") (name "Net-(U4-VFB)") (class "Default")
      (node (ref "R14") (pin "1") (pinfunction "1_1") (pintype "passive"))
      (node (ref "R15") (pin "1") (pinfunction "1_1") (pintype "passive"))
      (node (ref "U4") (pin "3") (pinfunction "VFB_3") (pintype "bidirectional"))
    )
    (net (code "48") (name "Net-(X2C-1)") (class "Default")
      (node (ref "L3") (pin "2") (pinfunction "2_2") (pintype "passive"))
      (node (ref "X2") (pin "3") (pinfunction "1_3") (pintype "passive"))
    )
    (net (code "49") (name "Net-(X4C-1)") (class "Default")
      (node (ref "R12") (pin "2") (pinfunction "2_2") (pintype "passive"))
      (node (ref "X4") (pin "3") (pinfunction "1_3") (pintype "passive"))
    )
    (net (code "50") (name "Net-(X4E-1)") (class "Default")
      (node (ref "R13") (pin "2") (pinfunction "2_2") (pintype "passive"))
      (node (ref "X4") (pin "5") (pinfunction "1_5") (pintype "passive"))
    )
    (net (code "51") (name "RELAY") (class "Default")
      (node (ref "R16") (pin "1") (pinfunction "1_1") (pintype "passive"))
      (node (ref "U1") (pin "22") (pinfunction "ADC7_22") (pintype "bidirectional"))
    )
    (net (code "52") (name "RST-AVR") (class "Default")
      (node (ref "J1") (pin "5") (pinfunction "5_5") (pintype "bidirectional"))
      (node (ref "R1") (pin "1") (pinfunction "1_1") (pintype "passive"))
      (node (ref "U1") (pin "29") (pinfunction "PC6(/RESET)_29") (pintype "bidirectional"))
    )
    (net (code "53") (name "RST-SI") (class "Default")
      (node (ref "R4") (pin "2") (pinfunction "2_2") (pintype "passive"))
      (node (ref "U1") (pin "9") (pinfunction "PD5(T1)_9") (pintype "bidirectional"))
      (node (ref "U2") (pin "5") (pinfunction "~{RST}_5") (pintype "bidirectional"))
    )
    (net (code "54") (name "RTS") (class "Default")
      (node (ref "J2") (pin "6") (pinfunction "6_6") (pintype "bidirectional"))
      (node (ref "U1") (pin "1") (pinfunction "PD3(INT1)_1") (pintype "bidirectional"))
    )
    (net (code "55") (name "RXD") (class "Default")
      (node (ref "J2") (pin "5") (pinfunction "5_5") (pintype "bidirectional"))
      (node (ref "U1") (pin "31") (pinfunction "PD1(TXD)_31") (pintype "bidirectional"))
    )
    (net (code "56") (name "SCK") (class "Default")
      (node (ref "J1") (pin "3") (pinfunction "3_3") (pintype "bidirectional"))
      (node (ref "U1") (pin "17") (pinfunction "PB5(SCK)_17") (pintype "bidirectional"))
    )
    (net (code "57") (name "SCL") (class "Default")
      (node (ref "R3") (pin "2") (pinfunction "2_2") (pintype "passive"))
      (node (ref "U1") (pin "28") (pinfunction "PC5(ADC5/SCL)_28") (pintype "bidirectional"))
      (node (ref "U2") (pin "7") (pinfunction "SCLK_7") (pintype "bidirectional"))
    )
    (net (code "58") (name "SDA") (class "Default")
      (node (ref "R2") (pin "2") (pinfunction "2_2") (pintype "passive"))
      (node (ref "U1") (pin "27") (pinfunction "PC4(ADC4/SDA)_27") (pintype "bidirectional"))
      (node (ref "U2") (pin "8") (pinfunction "SDIO_8") (pintype "bidirectional"))
    )
    (net (code "59") (name "TXD") (class "Default")
      (node (ref "J2") (pin "4") (pinfunction "4_4") (pintype "bidirectional"))
      (node (ref "U1") (pin "30") (pinfunction "PD0(RXD)_30") (pintype "bidirectional"))
    )
    (net (code "60") (name "unconnected-(U2-GPO1-Pad19)") (class "Default")
      (node (ref "U2") (pin "19") (pinfunction "GPO1_19") (pintype "bidirectional"))
    )
  )
)
